# parts_servo.net
KiCad netlist of a schematic drawn in EAGLE
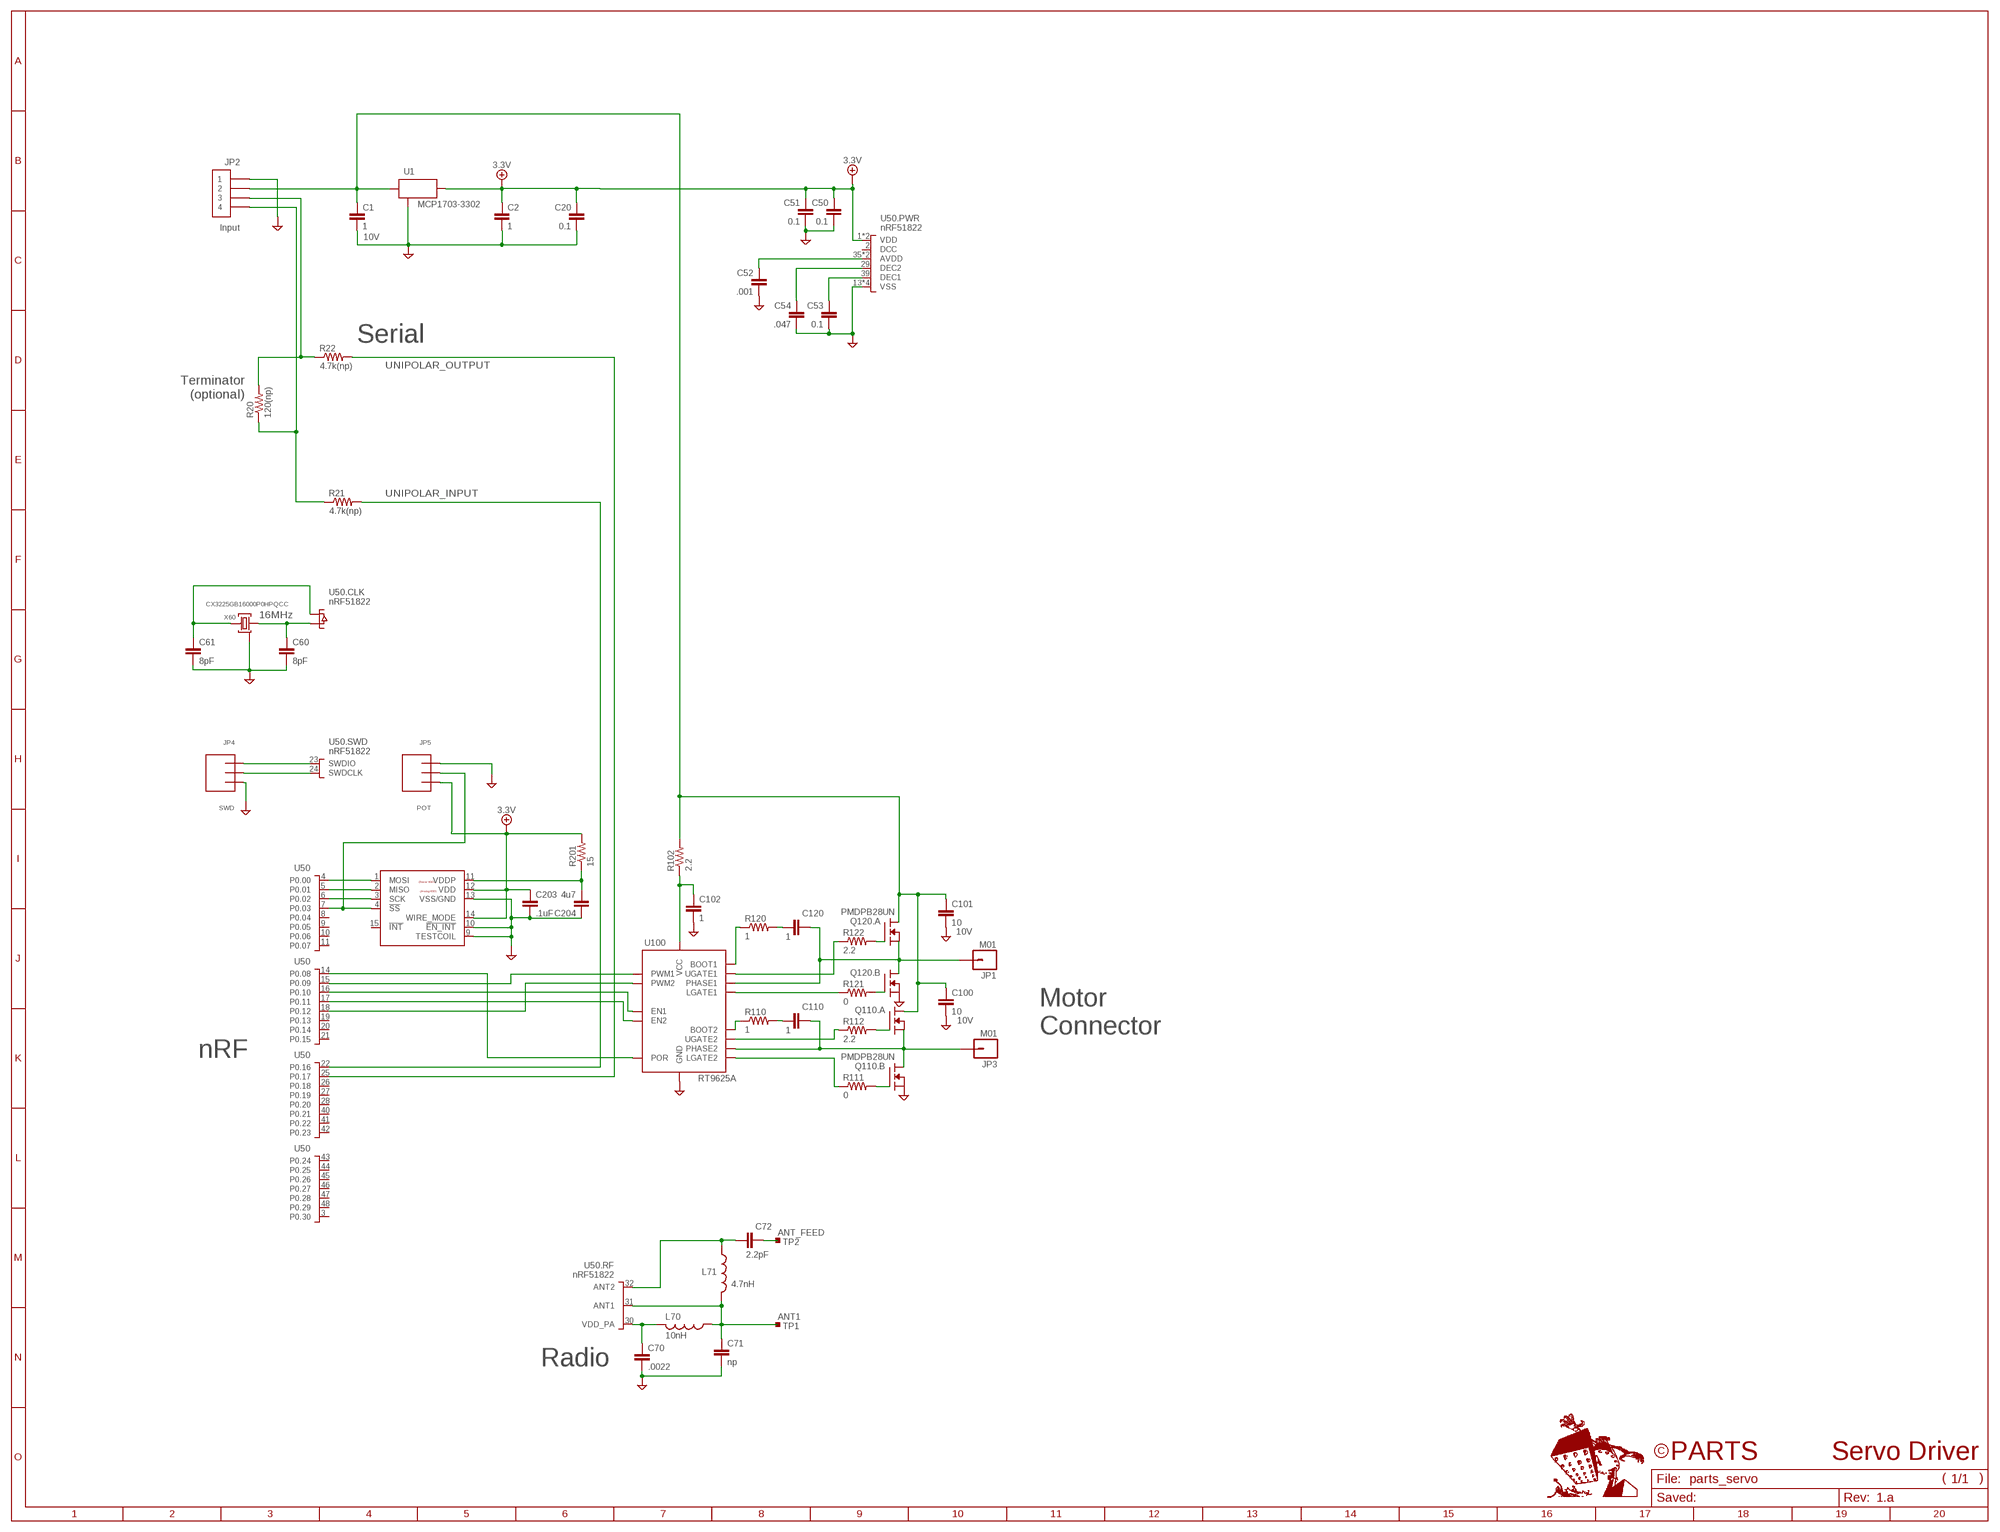
[diagram p0: schematic, sheet 1]

(export (version "E")
  (design (tool "Eeschema 10.0.6"))
  (components
    (comp (ref "C1")
      (value "1")
      (footprint "eagle-import:0402-B")
      (fields (field (name "VOLTAGE") "10V"))
      (libsource (lib "eagle-import") (part "C-EU0402-B"))
    )
    (comp (ref "C2")
      (value "1")
      (footprint "eagle-import:0402-B")
      (libsource (lib "eagle-import") (part "C-EU0402-B"))
    )
    (comp (ref "C20")
      (value "0.1")
      (footprint "eagle-import:0402-B")
      (libsource (lib "eagle-import") (part "C-EU0402-B"))
    )
    (comp (ref "C50")
      (value "0.1")
      (footprint "eagle-import:0402-B")
      (libsource (lib "eagle-import") (part "C-EU0402-B"))
    )
    (comp (ref "C51")
      (value "0.1")
      (footprint "eagle-import:0402-B")
      (libsource (lib "eagle-import") (part "C-EU0402-B"))
    )
    (comp (ref "C52")
      (value ".001")
      (footprint "eagle-import:0402-B")
      (libsource (lib "eagle-import") (part "C-EU0402-B"))
    )
    (comp (ref "C53")
      (value "0.1")
      (footprint "eagle-import:0402-B")
      (libsource (lib "eagle-import") (part "C-EU0402-B"))
    )
    (comp (ref "C54")
      (value ".047")
      (footprint "eagle-import:0402-B")
      (libsource (lib "eagle-import") (part "C-EU0402-B"))
    )
    (comp (ref "C60")
      (value "8pF")
      (footprint "eagle-import:0402-B")
      (libsource (lib "eagle-import") (part "C-EU0402-B"))
    )
    (comp (ref "C61")
      (value "8pF")
      (footprint "eagle-import:0402-B")
      (libsource (lib "eagle-import") (part "C-EU0402-B"))
    )
    (comp (ref "C70")
      (value ".0022")
      (footprint "eagle-import:0402-B")
      (libsource (lib "eagle-import") (part "C-EU0402-B"))
    )
    (comp (ref "C71")
      (value "np")
      (footprint "eagle-import:0402-B")
      (libsource (lib "eagle-import") (part "C-EU0402-B"))
    )
    (comp (ref "C72")
      (value "2.2pF")
      (footprint "eagle-import:0402-B")
      (libsource (lib "eagle-import") (part "C-EU0402-B"))
    )
    (comp (ref "C100")
      (value "10")
      (footprint "eagle-import:0805-B")
      (fields (field (name "VOLTAGE") "10V"))
      (libsource (lib "eagle-import") (part "C-EU0805-B"))
    )
    (comp (ref "C101")
      (value "10")
      (footprint "eagle-import:0805-B")
      (fields (field (name "VOLTAGE") "10V"))
      (libsource (lib "eagle-import") (part "C-EU0805-B"))
    )
    (comp (ref "C102")
      (value "1")
      (footprint "eagle-import:0402-B")
      (libsource (lib "eagle-import") (part "C-EU0402-B"))
    )
    (comp (ref "C110")
      (value "1")
      (footprint "eagle-import:0402-B")
      (libsource (lib "eagle-import") (part "C-EU0402-B"))
    )
    (comp (ref "C120")
      (value "1")
      (footprint "eagle-import:0402-B")
      (libsource (lib "eagle-import") (part "C-EU0402-B"))
    )
    (comp (ref "C203")
      (value ".1uF")
      (footprint "eagle-import:0402-B")
      (libsource (lib "eagle-import") (part "C-EU0402-B"))
    )
    (comp (ref "C204")
      (value "4u7")
      (footprint "eagle-import:0402-B")
      (libsource (lib "eagle-import") (part "C-EU0402-B"))
    )
    (comp (ref "JP1")
      (value "M01")
      (footprint "eagle-import:SMDMOTOR")
      (libsource (lib "eagle-import") (part "M01"))
    )
    (comp (ref "JP2")
      (value "Input")
      (footprint "eagle-import:SMD_1X4_HEADER")
      (libsource (lib "eagle-import") (part "SMD_1X4_HEADER"))
    )
    (comp (ref "JP3")
      (value "M01")
      (footprint "eagle-import:SMDMOTOR")
      (libsource (lib "eagle-import") (part "M01"))
    )
    (comp (ref "JP4")
      (value "SWD")
      (footprint "eagle-import:SMD_1X3_HEADER")
      (libsource (lib "eagle-import") (part "SMD_1X3_HEADER"))
    )
    (comp (ref "JP5")
      (value "POT")
      (footprint "eagle-import:SMD_1X3_PADS")
      (libsource (lib "eagle-import") (part "SMD_1X3_HEADERSMDLARGEPADS"))
    )
    (comp (ref "L70")
      (value "10nH")
      (footprint "eagle-import:0402-B")
      (libsource (lib "eagle-import") (part "L-US0402-B"))
    )
    (comp (ref "L71")
      (value "4.7nH")
      (footprint "eagle-import:0402-B")
      (libsource (lib "eagle-import") (part "L-US0402-B"))
    )
    (comp (ref "Q110")
      (value "PMDPB28UN")
      (footprint "eagle-import:DFN-6(2X2)+2EP(TRANSISTOR)")
      (libsource (lib "eagle-import") (part "NFET-DUAL-DFN-6(2X2)+2PADS"))
    )
    (comp (ref "Q120")
      (value "PMDPB28UN")
      (footprint "eagle-import:DFN-6(2X2)+2EP(TRANSISTOR)")
      (libsource (lib "eagle-import") (part "NFET-DUAL-DFN-6(2X2)+2PADS"))
    )
    (comp (ref "R20")
      (value "120(np)")
      (footprint "eagle-import:0402-B")
      (libsource (lib "eagle-import") (part "R-US_0402-B"))
    )
    (comp (ref "R21")
      (value "4.7k(np)")
      (footprint "eagle-import:0402-B")
      (libsource (lib "eagle-import") (part "R-US_0402-B"))
    )
    (comp (ref "R22")
      (value "4.7k(np)")
      (footprint "eagle-import:0402-B")
      (libsource (lib "eagle-import") (part "R-US_0402-B"))
    )
    (comp (ref "R102")
      (value "2.2")
      (footprint "eagle-import:0402-B")
      (libsource (lib "eagle-import") (part "R-US_0402-B"))
    )
    (comp (ref "R110")
      (value "1")
      (footprint "eagle-import:0402-B")
      (libsource (lib "eagle-import") (part "R-US_0402-B"))
    )
    (comp (ref "R111")
      (value "0")
      (footprint "eagle-import:0402-B")
      (libsource (lib "eagle-import") (part "R-US_0402-B"))
    )
    (comp (ref "R112")
      (value "2.2")
      (footprint "eagle-import:0402-B")
      (libsource (lib "eagle-import") (part "R-US_0402-B"))
    )
    (comp (ref "R120")
      (value "1")
      (footprint "eagle-import:0402-B")
      (libsource (lib "eagle-import") (part "R-US_0402-B"))
    )
    (comp (ref "R121")
      (value "0")
      (footprint "eagle-import:0402-B")
      (libsource (lib "eagle-import") (part "R-US_0402-B"))
    )
    (comp (ref "R122")
      (value "2.2")
      (footprint "eagle-import:0402-B")
      (libsource (lib "eagle-import") (part "R-US_0402-B"))
    )
    (comp (ref "R201")
      (value "15")
      (footprint "eagle-import:0402-B")
      (libsource (lib "eagle-import") (part "R-US_0402-B"))
    )
    (comp (ref "TP1")
      (value "ANT1")
      (footprint "eagle-import:TESTPOINT-(1X1)CREAMED")
      (libsource (lib "eagle-import") (part "TESTPAD-(1X1)CREAMED"))
    )
    (comp (ref "TP2")
      (value "ANT_FEED")
      (footprint "eagle-import:TESTPOINT-(1X1)CREAMED")
      (libsource (lib "eagle-import") (part "TESTPAD-(1X1)CREAMED"))
    )
    (comp (ref "U1")
      (value "MCP1703-3302")
      (footprint "eagle-import:DFN-8(2X3)+EP")
      (libsource (lib "eagle-import") (part "VOLTAGE_REGULATOR-3_TERMINAL"))
    )
    (comp (ref "U50")
      (value "nRF51822")
      (footprint "eagle-import:DFN-48(6X6)+EP")
      (fields (field (name "SWDIO") "(nRST)"))
      (libsource (lib "eagle-import") (part "NRF51822-QFN-48(6X6)"))
    )
    (comp (ref "U100")
      (value "RT9625A")
      (footprint "eagle-import:QFN-16(4X4)+EP")
      (libsource (lib "eagle-import") (part "HALF_BRIDGE_DRIVER-DUAL-QFN-16(4X4)"))
    )
    (comp (ref "U200")
      (value "AS5050")
      (footprint "eagle-import:QFN16_4X4")
      (libsource (lib "eagle-import") (part "AS5050"))
    )
    (comp (ref "X60")
      (value "CX3225GB16000P0HPQCC")
      (footprint "eagle-import:CRYSTAL-3.2X2.5(4_TERMINAL)")
      (fields (field (name "FREQUENCY") "16MHz"))
      (libsource (lib "eagle-import") (part "CRYSTAL_SHIELDED-3.2X2.5"))
    )
  )
  (nets
    (net (code "1") (name "/UNIPOLAR_INPUT") (class "Default")
      (node (ref "R21") (pin "2") (pinfunction "2_2") (pintype "passive"))
      (node (ref "U50") (pin "22") (pinfunction "P0.16_22") (pintype "bidirectional"))
    )
    (net (code "2") (name "/UNIPOLAR_OUTPUT") (class "Default")
      (node (ref "R22") (pin "2") (pinfunction "2_2") (pintype "passive"))
      (node (ref "U50") (pin "25") (pinfunction "P0.17_25") (pintype "bidirectional"))
    )
    (net (code "3") (name "3.3V") (class "Default")
      (node (ref "C2") (pin "1") (pinfunction "1_1") (pintype "passive"))
      (node (ref "C20") (pin "1") (pinfunction "1_1") (pintype "passive"))
      (node (ref "C203") (pin "1") (pinfunction "1_1") (pintype "passive"))
      (node (ref "C50") (pin "1") (pinfunction "1_1") (pintype "passive"))
      (node (ref "C51") (pin "1") (pinfunction "1_1") (pintype "passive"))
      (node (ref "JP5") (pin "3") (pinfunction "3_3") (pintype "bidirectional"))
      (node (ref "R201") (pin "2") (pinfunction "2_2") (pintype "passive"))
      (node (ref "U1") (pin "1") (pinfunction "OUT_1") (pintype "power_in"))
      (node (ref "U200") (pin "12") (pinfunction "VDD_12") (pintype "bidirectional"))
      (node (ref "U200") (pin "14") (pinfunction "WIRE_MODE_14") (pintype "bidirectional"))
      (node (ref "U50") (pin "1") (pinfunction "VDD_1") (pintype "power_in"))
      (node (ref "U50") (pin "12") (pinfunction "VDD_12") (pintype "power_in"))
    )
    (net (code "4") (name "GND_TRIANGLE-GND") (class "Default")
      (node (ref "C1") (pin "2") (pinfunction "2_2") (pintype "passive"))
      (node (ref "C100") (pin "2") (pinfunction "2_2") (pintype "passive"))
      (node (ref "C101") (pin "2") (pinfunction "2_2") (pintype "passive"))
      (node (ref "C102") (pin "2") (pinfunction "2_2") (pintype "passive"))
      (node (ref "C2") (pin "2") (pinfunction "2_2") (pintype "passive"))
      (node (ref "C20") (pin "2") (pinfunction "2_2") (pintype "passive"))
      (node (ref "C203") (pin "2") (pinfunction "2_2") (pintype "passive"))
      (node (ref "C204") (pin "1") (pinfunction "1_1") (pintype "passive"))
      (node (ref "C50") (pin "2") (pinfunction "2_2") (pintype "passive"))
      (node (ref "C51") (pin "2") (pinfunction "2_2") (pintype "passive"))
      (node (ref "C52") (pin "2") (pinfunction "2_2") (pintype "passive"))
      (node (ref "C53") (pin "2") (pinfunction "2_2") (pintype "passive"))
      (node (ref "C54") (pin "2") (pinfunction "2_2") (pintype "passive"))
      (node (ref "C60") (pin "2") (pinfunction "2_2") (pintype "passive"))
      (node (ref "C61") (pin "2") (pinfunction "2_2") (pintype "passive"))
      (node (ref "C70") (pin "2") (pinfunction "2_2") (pintype "passive"))
      (node (ref "C71") (pin "2") (pinfunction "2_2") (pintype "passive"))
      (node (ref "JP2") (pin "1") (pinfunction "1_1") (pintype "bidirectional"))
      (node (ref "JP4") (pin "P$3") (pinfunction "3_P$3") (pintype "bidirectional"))
      (node (ref "JP5") (pin "1") (pinfunction "1_1") (pintype "bidirectional"))
      (node (ref "Q110") (pin "4") (pinfunction "S_4") (pintype "passive"))
      (node (ref "Q120") (pin "4") (pinfunction "S_4") (pintype "passive"))
      (node (ref "U1") (pin "4") (pinfunction "GND_4") (pintype "power_in"))
      (node (ref "U1") (pin "PAD") (pinfunction "GND_PAD") (pintype "power_in"))
      (node (ref "U100") (pin "13") (pinfunction "GND_13") (pintype "power_in"))
      (node (ref "U100") (pin "2") (pinfunction "GND_2") (pintype "power_in"))
      (node (ref "U100") (pin "PAD") (pinfunction "GND_PAD") (pintype "power_in"))
      (node (ref "U200") (pin "10") (pinfunction "~{EN_INT}_10") (pintype "bidirectional"))
      (node (ref "U200") (pin "13") (pinfunction "VSS/GND_13") (pintype "bidirectional"))
      (node (ref "U200") (pin "9") (pinfunction "TESTCOIL_9") (pintype "bidirectional"))
      (node (ref "U50") (pin "13") (pinfunction "VSS_13") (pintype "power_in"))
      (node (ref "U50") (pin "33") (pinfunction "VSS_33") (pintype "power_in"))
      (node (ref "U50") (pin "34") (pinfunction "VSS_34") (pintype "power_in"))
      (node (ref "U50") (pin "PAD") (pinfunction "VSS_PAD") (pintype "power_in"))
      (node (ref "X60") (pin "2") (pinfunction "SHIELD_2") (pintype "passive"))
      (node (ref "X60") (pin "4") (pinfunction "SHIELD_4") (pintype "passive"))
    )
    (net (code "5") (name "Net-(C52-Pad1)") (class "Default")
      (node (ref "C52") (pin "1") (pinfunction "1_1") (pintype "passive"))
      (node (ref "U50") (pin "35") (pinfunction "AVDD_35") (pintype "power_in"))
      (node (ref "U50") (pin "36") (pinfunction "AVDD_36") (pintype "power_in"))
    )
    (net (code "6") (name "Net-(C72-Pad2)") (class "Default")
      (node (ref "C72") (pin "2") (pinfunction "2_2") (pintype "passive"))
      (node (ref "TP2") (pin "TP") (pinfunction "TP_TP") (pintype "passive"))
    )
    (net (code "7") (name "Net-(C110-Pad1)") (class "Default")
      (node (ref "C110") (pin "1") (pinfunction "1_1") (pintype "passive"))
      (node (ref "R110") (pin "2") (pinfunction "2_2") (pintype "passive"))
    )
    (net (code "8") (name "Net-(C120-Pad1)") (class "Default")
      (node (ref "C120") (pin "1") (pinfunction "1_1") (pintype "passive"))
      (node (ref "R120") (pin "2") (pinfunction "2_2") (pintype "passive"))
    )
    (net (code "9") (name "Net-(JP2-Pad3)") (class "Default")
      (node (ref "JP2") (pin "3") (pinfunction "3_3") (pintype "bidirectional"))
      (node (ref "R20") (pin "2") (pinfunction "2_2") (pintype "passive"))
      (node (ref "R22") (pin "1") (pinfunction "1_1") (pintype "passive"))
    )
    (net (code "10") (name "Net-(JP2-Pad4)") (class "Default")
      (node (ref "JP2") (pin "4") (pinfunction "4_4") (pintype "bidirectional"))
      (node (ref "R20") (pin "1") (pinfunction "1_1") (pintype "passive"))
      (node (ref "R21") (pin "1") (pinfunction "1_1") (pintype "passive"))
    )
    (net (code "11") (name "Net-(JP4-1)") (class "Default")
      (node (ref "JP4") (pin "P$1") (pinfunction "1_P$1") (pintype "bidirectional"))
      (node (ref "U50") (pin "23") (pinfunction "SWDIO_23") (pintype "bidirectional"))
    )
    (net (code "12") (name "Net-(JP4-2)") (class "Default")
      (node (ref "JP4") (pin "P$2") (pinfunction "2_P$2") (pintype "bidirectional"))
      (node (ref "U50") (pin "24") (pinfunction "SWDCLK_24") (pintype "input"))
    )
    (net (code "13") (name "Net-(Q110A-G)") (class "Default")
      (node (ref "Q110") (pin "2") (pinfunction "G_2") (pintype "passive"))
      (node (ref "R112") (pin "2") (pinfunction "2_2") (pintype "passive"))
    )
    (net (code "14") (name "Net-(Q110A-S)") (class "Default")
      (node (ref "C110") (pin "2") (pinfunction "2_2") (pintype "passive"))
      (node (ref "JP3") (pin "1") (pinfunction "1_1") (pintype "passive"))
      (node (ref "Q110") (pin "1") (pinfunction "S_1") (pintype "passive"))
      (node (ref "Q110") (pin "3") (pinfunction "D_3") (pintype "passive"))
      (node (ref "Q110") (pin "P8") (pinfunction "D_P8") (pintype "passive"))
      (node (ref "U100") (pin "15") (pinfunction "PHASE2_15") (pintype "input"))
    )
    (net (code "15") (name "Net-(Q110B-G)") (class "Default")
      (node (ref "Q110") (pin "5") (pinfunction "G_5") (pintype "passive"))
      (node (ref "R111") (pin "2") (pinfunction "2_2") (pintype "passive"))
    )
    (net (code "16") (name "Net-(Q120A-G)") (class "Default")
      (node (ref "Q120") (pin "2") (pinfunction "G_2") (pintype "passive"))
      (node (ref "R122") (pin "2") (pinfunction "2_2") (pintype "passive"))
    )
    (net (code "17") (name "Net-(Q120A-S)") (class "Default")
      (node (ref "C120") (pin "2") (pinfunction "2_2") (pintype "passive"))
      (node (ref "JP1") (pin "1") (pinfunction "1_1") (pintype "passive"))
      (node (ref "Q120") (pin "1") (pinfunction "S_1") (pintype "passive"))
      (node (ref "Q120") (pin "3") (pinfunction "D_3") (pintype "passive"))
      (node (ref "Q120") (pin "P8") (pinfunction "D_P8") (pintype "passive"))
      (node (ref "U100") (pin "10") (pinfunction "PHASE1_10") (pintype "input"))
    )
    (net (code "18") (name "Net-(Q120B-G)") (class "Default")
      (node (ref "Q120") (pin "5") (pinfunction "G_5") (pintype "passive"))
      (node (ref "R121") (pin "2") (pinfunction "2_2") (pintype "passive"))
    )
    (net (code "19") (name "Net-(U1-IN)") (class "Default")
      (node (ref "C1") (pin "1") (pinfunction "1_1") (pintype "passive"))
      (node (ref "C100") (pin "1") (pinfunction "1_1") (pintype "passive"))
      (node (ref "C101") (pin "1") (pinfunction "1_1") (pintype "passive"))
      (node (ref "JP2") (pin "2") (pinfunction "2_2") (pintype "bidirectional"))
      (node (ref "Q110") (pin "6") (pinfunction "D_6") (pintype "passive"))
      (node (ref "Q110") (pin "P7") (pinfunction "D_P7") (pintype "passive"))
      (node (ref "Q120") (pin "6") (pinfunction "D_6") (pintype "passive"))
      (node (ref "Q120") (pin "P7") (pinfunction "D_P7") (pintype "passive"))
      (node (ref "R102") (pin "2") (pinfunction "2_2") (pintype "passive"))
      (node (ref "U1") (pin "8") (pinfunction "IN_8") (pintype "power_in"))
    )
    (net (code "20") (name "Net-(U50A-CLKIN)") (class "Default")
      (node (ref "C60") (pin "1") (pinfunction "1_1") (pintype "passive"))
      (node (ref "U50") (pin "37") (pinfunction "CLKIN_37") (pintype "input"))
      (node (ref "X60") (pin "1") (pinfunction "1_1") (pintype "passive"))
    )
    (net (code "21") (name "Net-(U50A-CLKOUT)") (class "Default")
      (node (ref "C61") (pin "1") (pinfunction "1_1") (pintype "passive"))
      (node (ref "U50") (pin "38") (pinfunction "CLKOUT_38") (pintype "output"))
      (node (ref "X60") (pin "3") (pinfunction "2_3") (pintype "passive"))
    )
    (net (code "22") (name "Net-(U50B-DEC1)") (class "Default")
      (node (ref "C53") (pin "1") (pinfunction "1_1") (pintype "passive"))
      (node (ref "U50") (pin "39") (pinfunction "DEC1_39") (pintype "passive"))
    )
    (net (code "23") (name "Net-(U50B-DEC2)") (class "Default")
      (node (ref "C54") (pin "1") (pinfunction "1_1") (pintype "passive"))
      (node (ref "U50") (pin "29") (pinfunction "DEC2_29") (pintype "passive"))
    )
    (net (code "24") (name "Net-(U50C-ANT1)") (class "Default")
      (node (ref "C71") (pin "1") (pinfunction "1_1") (pintype "passive"))
      (node (ref "L70") (pin "1") (pinfunction "1_1") (pintype "passive"))
      (node (ref "L71") (pin "2") (pinfunction "2_2") (pintype "passive"))
      (node (ref "TP1") (pin "TP") (pinfunction "TP_TP") (pintype "passive"))
      (node (ref "U50") (pin "31") (pinfunction "ANT1_31") (pintype "passive"))
    )
    (net (code "25") (name "Net-(U50C-ANT2)") (class "Default")
      (node (ref "C72") (pin "1") (pinfunction "1_1") (pintype "passive"))
      (node (ref "L71") (pin "1") (pinfunction "1_1") (pintype "passive"))
      (node (ref "U50") (pin "32") (pinfunction "ANT2_32") (pintype "passive"))
    )
    (net (code "26") (name "Net-(U50C-VDD_PA)") (class "Default")
      (node (ref "C70") (pin "1") (pinfunction "1_1") (pintype "passive"))
      (node (ref "L70") (pin "2") (pinfunction "2_2") (pintype "passive"))
      (node (ref "U50") (pin "30") (pinfunction "VDD_PA_30") (pintype "passive"))
    )
    (net (code "27") (name "Net-(U100-BOOT1)") (class "Default")
      (node (ref "R120") (pin "1") (pinfunction "1_1") (pintype "passive"))
      (node (ref "U100") (pin "8") (pinfunction "BOOT1_8") (pintype "passive"))
    )
    (net (code "28") (name "Net-(U100-BOOT2)") (class "Default")
      (node (ref "R110") (pin "1") (pinfunction "1_1") (pintype "passive"))
      (node (ref "U100") (pin "1") (pinfunction "BOOT2_1") (pintype "output"))
    )
    (net (code "29") (name "Net-(U100-EN1)") (class "Default")
      (node (ref "U100") (pin "5") (pinfunction "EN1_5") (pintype "input"))
      (node (ref "U50") (pin "16") (pinfunction "P0.10_16") (pintype "bidirectional"))
    )
    (net (code "30") (name "Net-(U100-EN2)") (class "Default")
      (node (ref "U100") (pin "4") (pinfunction "EN2_4") (pintype "input"))
      (node (ref "U50") (pin "17") (pinfunction "P0.11_17") (pintype "bidirectional"))
    )
    (net (code "31") (name "Net-(U100-LGATE1)") (class "Default")
      (node (ref "R121") (pin "1") (pinfunction "1_1") (pintype "passive"))
      (node (ref "U100") (pin "11") (pinfunction "LGATE1_11") (pintype "output"))
    )
    (net (code "32") (name "Net-(U100-LGATE2)") (class "Default")
      (node (ref "R111") (pin "1") (pinfunction "1_1") (pintype "passive"))
      (node (ref "U100") (pin "14") (pinfunction "LGATE2_14") (pintype "passive"))
    )
    (net (code "33") (name "Net-(U100-POR)") (class "Default")
      (node (ref "U100") (pin "7") (pinfunction "POR_7") (pintype "bidirectional"))
      (node (ref "U50") (pin "14") (pinfunction "P0.08_14") (pintype "bidirectional"))
    )
    (net (code "34") (name "Net-(U100-PWM1)") (class "Default")
      (node (ref "U100") (pin "6") (pinfunction "PWM1_6") (pintype "input"))
      (node (ref "U50") (pin "15") (pinfunction "P0.09_15") (pintype "bidirectional"))
    )
    (net (code "35") (name "Net-(U100-PWM2)") (class "Default")
      (node (ref "U100") (pin "3") (pinfunction "PWM2_3") (pintype "input"))
      (node (ref "U50") (pin "18") (pinfunction "P0.12_18") (pintype "bidirectional"))
    )
    (net (code "36") (name "Net-(U100-UGATE1)") (class "Default")
      (node (ref "R122") (pin "1") (pinfunction "1_1") (pintype "passive"))
      (node (ref "U100") (pin "9") (pinfunction "UGATE1_9") (pintype "output"))
    )
    (net (code "37") (name "Net-(U100-UGATE2)") (class "Default")
      (node (ref "R112") (pin "1") (pinfunction "1_1") (pintype "passive"))
      (node (ref "U100") (pin "16") (pinfunction "UGATE2_16") (pintype "output"))
    )
    (net (code "38") (name "Net-(U100-VCC)") (class "Default")
      (node (ref "C102") (pin "1") (pinfunction "1_1") (pintype "passive"))
      (node (ref "R102") (pin "1") (pinfunction "1_1") (pintype "passive"))
      (node (ref "U100") (pin "12") (pinfunction "VCC_12") (pintype "power_in"))
    )
    (net (code "39") (name "Net-(U200-MISO)") (class "Default")
      (node (ref "U200") (pin "2") (pinfunction "MISO_2") (pintype "bidirectional"))
      (node (ref "U50") (pin "5") (pinfunction "P0.01_5") (pintype "bidirectional"))
    )
    (net (code "40") (name "Net-(U200-MOSI)") (class "Default")
      (node (ref "U200") (pin "1") (pinfunction "MOSI_1") (pintype "bidirectional"))
      (node (ref "U50") (pin "4") (pinfunction "P0.00_4") (pintype "bidirectional"))
    )
    (net (code "41") (name "Net-(U200-SCK)") (class "Default")
      (node (ref "U200") (pin "3") (pinfunction "SCK_3") (pintype "bidirectional"))
      (node (ref "U50") (pin "6") (pinfunction "P0.02_6") (pintype "bidirectional"))
    )
    (net (code "42") (name "Net-(U200-VDDP)") (class "Default")
      (node (ref "C204") (pin "2") (pinfunction "2_2") (pintype "passive"))
      (node (ref "R201") (pin "1") (pinfunction "1_1") (pintype "passive"))
      (node (ref "U200") (pin "11") (pinfunction "VDDP_11") (pintype "bidirectional"))
    )
    (net (code "43") (name "Net-(U200-~{SS})") (class "Default")
      (node (ref "JP5") (pin "2") (pinfunction "2_2") (pintype "bidirectional"))
      (node (ref "U200") (pin "4") (pinfunction "~{SS}_4") (pintype "bidirectional"))
      (node (ref "U50") (pin "7") (pinfunction "P0.03_7") (pintype "bidirectional"))
    )
    (net (code "44") (name "unconnected-(U50B-DCC-Pad2)") (class "Default")
      (node (ref "U50") (pin "2") (pinfunction "DCC_2") (pintype "passive"))
    )
    (net (code "45") (name "unconnected-(U50E-P0.04-Pad8)") (class "Default")
      (node (ref "U50") (pin "8") (pinfunction "P0.04_8") (pintype "bidirectional"))
    )
    (net (code "46") (name "unconnected-(U50E-P0.05-Pad9)") (class "Default")
      (node (ref "U50") (pin "9") (pinfunction "P0.05_9") (pintype "bidirectional"))
    )
    (net (code "47") (name "unconnected-(U50E-P0.06-Pad10)") (class "Default")
      (node (ref "U50") (pin "10") (pinfunction "P0.06_10") (pintype "bidirectional"))
    )
    (net (code "48") (name "unconnected-(U50E-P0.07-Pad11)") (class "Default")
      (node (ref "U50") (pin "11") (pinfunction "P0.07_11") (pintype "bidirectional"))
    )
    (net (code "49") (name "unconnected-(U50F-P0.13-Pad19)") (class "Default")
      (node (ref "U50") (pin "19") (pinfunction "P0.13_19") (pintype "bidirectional"))
    )
    (net (code "50") (name "unconnected-(U50F-P0.14-Pad20)") (class "Default")
      (node (ref "U50") (pin "20") (pinfunction "P0.14_20") (pintype "bidirectional"))
    )
    (net (code "51") (name "unconnected-(U50F-P0.15-Pad21)") (class "Default")
      (node (ref "U50") (pin "21") (pinfunction "P0.15_21") (pintype "bidirectional"))
    )
    (net (code "52") (name "unconnected-(U50G-P0.18-Pad26)") (class "Default")
      (node (ref "U50") (pin "26") (pinfunction "P0.18_26") (pintype "bidirectional"))
    )
    (net (code "53") (name "unconnected-(U50G-P0.19-Pad27)") (class "Default")
      (node (ref "U50") (pin "27") (pinfunction "P0.19_27") (pintype "bidirectional"))
    )
    (net (code "54") (name "unconnected-(U50G-P0.20-Pad28)") (class "Default")
      (node (ref "U50") (pin "28") (pinfunction "P0.20_28") (pintype "bidirectional"))
    )
    (net (code "55") (name "unconnected-(U50G-P0.21-Pad40)") (class "Default")
      (node (ref "U50") (pin "40") (pinfunction "P0.21_40") (pintype "bidirectional"))
    )
    (net (code "56") (name "unconnected-(U50G-P0.22-Pad41)") (class "Default")
      (node (ref "U50") (pin "41") (pinfunction "P0.22_41") (pintype "bidirectional"))
    )
    (net (code "57") (name "unconnected-(U50G-P0.23-Pad42)") (class "Default")
      (node (ref "U50") (pin "42") (pinfunction "P0.23_42") (pintype "bidirectional"))
    )
    (net (code "58") (name "unconnected-(U50H-P0.24-Pad43)") (class "Default")
      (node (ref "U50") (pin "43") (pinfunction "P0.24_43") (pintype "bidirectional"))
    )
    (net (code "59") (name "unconnected-(U50H-P0.25-Pad44)") (class "Default")
      (node (ref "U50") (pin "44") (pinfunction "P0.25_44") (pintype "bidirectional"))
    )
    (net (code "60") (name "unconnected-(U50H-P0.26-Pad45)") (class "Default")
      (node (ref "U50") (pin "45") (pinfunction "P0.26_45") (pintype "bidirectional"))
    )
    (net (code "61") (name "unconnected-(U50H-P0.27-Pad46)") (class "Default")
      (node (ref "U50") (pin "46") (pinfunction "P0.27_46") (pintype "bidirectional"))
    )
    (net (code "62") (name "unconnected-(U50H-P0.28-Pad47)") (class "Default")
      (node (ref "U50") (pin "47") (pinfunction "P0.28_47") (pintype "bidirectional"))
    )
    (net (code "63") (name "unconnected-(U50H-P0.29-Pad48)") (class "Default")
      (node (ref "U50") (pin "48") (pinfunction "P0.29_48") (pintype "bidirectional"))
    )
    (net (code "64") (name "unconnected-(U50H-P0.30-Pad3)") (class "Default")
      (node (ref "U50") (pin "3") (pinfunction "P0.30_3") (pintype "bidirectional"))
    )
    (net (code "65") (name "unconnected-(U200-~{INT}-Pad15)") (class "Default")
      (node (ref "U200") (pin "15") (pinfunction "~{INT}_15") (pintype "bidirectional"))
    )
  )
)
